# Sensor.net
KiCad netlist of a schematic drawn in EAGLE
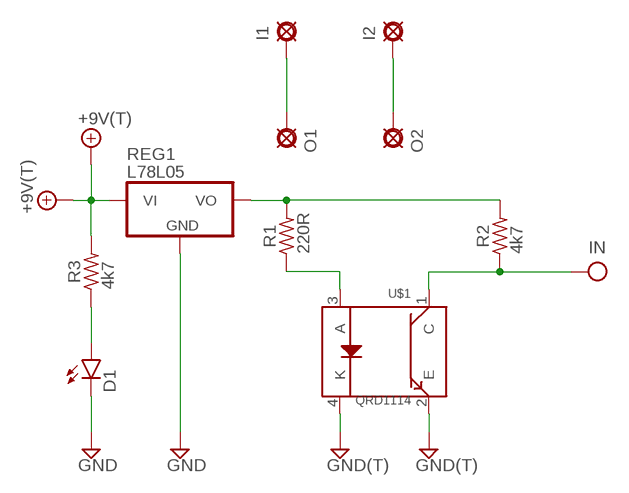
[diagram p0: schematic, sheet 1]

(export (version "E")
  (design (tool "Eeschema 10.0.6"))
  (components
    (comp (ref "+9V")
      (value "+9V(T)")
      (footprint "eagle-import:SQUARE")
      (libsource (lib "eagle-import") (part "+9V(T)"))
    )
    (comp (ref "+9V1")
      (value "+9V(T)")
      (footprint "eagle-import:SQUARE")
      (libsource (lib "eagle-import") (part "+9V(T)"))
    )
    (comp (ref "D1")
      (value "LED3MM")
      (footprint "eagle-import:LED3MM")
      (libsource (lib "eagle-import") (part "LED3MM"))
    )
    (comp (ref "G")
      (value "GND(T)")
      (footprint "eagle-import:SQUARE")
      (libsource (lib "eagle-import") (part "GND(T)"))
    )
    (comp (ref "G2")
      (value "GND(T)")
      (footprint "eagle-import:SQUARE")
      (libsource (lib "eagle-import") (part "GND(T)"))
    )
    (comp (ref "I1")
      (value "PAD")
      (footprint "eagle-import:SQUARE")
      (libsource (lib "eagle-import") (part "PAD"))
    )
    (comp (ref "I2")
      (value "PAD")
      (footprint "eagle-import:SQUARE")
      (libsource (lib "eagle-import") (part "PAD"))
    )
    (comp (ref "IN")
      (value "OUT(T)")
      (footprint "eagle-import:SQUARE")
      (libsource (lib "eagle-import") (part "OUT(T)"))
    )
    (comp (ref "O1")
      (value "PAD")
      (footprint "eagle-import:SQUARE")
      (libsource (lib "eagle-import") (part "PAD"))
    )
    (comp (ref "O2")
      (value "PAD")
      (footprint "eagle-import:SQUARE")
      (libsource (lib "eagle-import") (part "PAD"))
    )
    (comp (ref "R1")
      (value "220R")
      (footprint "eagle-import:R0207_3")
      (libsource (lib "eagle-import") (part "6MM.3"))
    )
    (comp (ref "R2")
      (value "4k7")
      (footprint "eagle-import:R0207_3")
      (libsource (lib "eagle-import") (part "6MM.3"))
    )
    (comp (ref "R3")
      (value "4k7")
      (footprint "eagle-import:R0207_3")
      (libsource (lib "eagle-import") (part "6MM.3"))
    )
    (comp (ref "REG1")
      (value "L78L05")
      (footprint "eagle-import:TO92-")
      (libsource (lib "eagle-import") (part "7805"))
    )
    (comp (ref "U$1")
      (value "QRD1114")
      (footprint "eagle-import:QRD1114")
      (libsource (lib "eagle-import") (part "QRD1114"))
    )
  )
  (nets
    (net (code "1") (name "+9V(T)") (class "Default")
      (node (ref "+9V") (pin "1") (pinfunction "+9V_1") (pintype "power_in"))
      (node (ref "+9V1") (pin "1") (pinfunction "+9V_1") (pintype "power_in"))
      (node (ref "R3") (pin "2") (pinfunction "2_2") (pintype "passive"))
      (node (ref "REG1") (pin "1") (pinfunction "VI_1") (pintype "input"))
    )
    (net (code "2") (name "GND") (class "Default")
      (node (ref "D1") (pin "K") (pinfunction "C_K") (pintype "passive"))
      (node (ref "G") (pin "1") (pinfunction "GND_1") (pintype "power_in"))
      (node (ref "G2") (pin "1") (pinfunction "GND_1") (pintype "power_in"))
      (node (ref "REG1") (pin "2") (pinfunction "GND_2") (pintype "passive"))
      (node (ref "U$1") (pin "2") (pinfunction "E_2") (pintype "bidirectional"))
      (node (ref "U$1") (pin "4") (pinfunction "K_4") (pintype "bidirectional"))
    )
    (net (code "3") (name "Net-(D1-PadA)") (class "Default")
      (node (ref "D1") (pin "A") (pinfunction "A_A") (pintype "passive"))
      (node (ref "R3") (pin "1") (pinfunction "1_1") (pintype "passive"))
    )
    (net (code "4") (name "Net-(I1-PAD)") (class "Default")
      (node (ref "I1") (pin "1") (pinfunction "PAD_1") (pintype "passive"))
      (node (ref "O1") (pin "1") (pinfunction "PAD_1") (pintype "passive"))
    )
    (net (code "5") (name "Net-(I2-PAD)") (class "Default")
      (node (ref "I2") (pin "1") (pinfunction "PAD_1") (pintype "passive"))
      (node (ref "O2") (pin "1") (pinfunction "PAD_1") (pintype "passive"))
    )
    (net (code "6") (name "Net-(REG1-VO)") (class "Default")
      (node (ref "R1") (pin "2") (pinfunction "2_2") (pintype "passive"))
      (node (ref "R2") (pin "2") (pinfunction "2_2") (pintype "passive"))
      (node (ref "REG1") (pin "3") (pinfunction "VO_3") (pintype "passive"))
    )
    (net (code "7") (name "Net-(U$1-A)") (class "Default")
      (node (ref "R1") (pin "1") (pinfunction "1_1") (pintype "passive"))
      (node (ref "U$1") (pin "3") (pinfunction "A_3") (pintype "bidirectional"))
    )
    (net (code "8") (name "OUT(T)") (class "Default")
      (node (ref "IN") (pin "1") (pinfunction "OUT_1") (pintype "power_in"))
      (node (ref "R2") (pin "1") (pinfunction "1_1") (pintype "passive"))
      (node (ref "U$1") (pin "1") (pinfunction "C_1") (pintype "bidirectional"))
    )
  )
)
